# 04_EEPROM_FLASH.net
KiCad netlist of a schematic drawn in Altium Designer
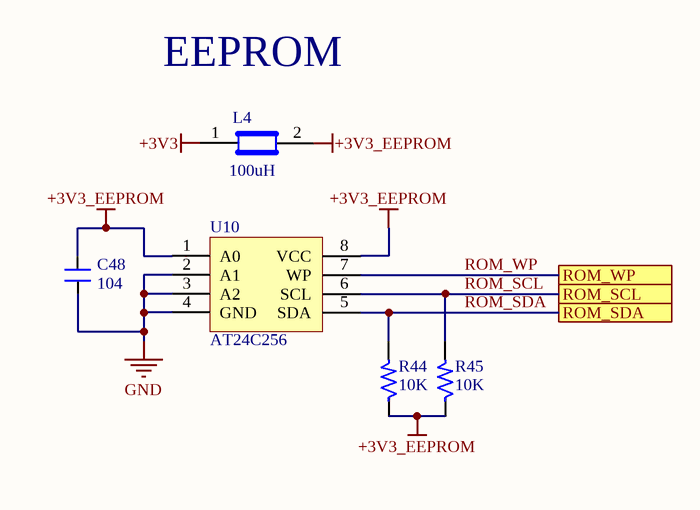
[diagram p0: [04] EEPROM_FLASH.SchDoc]

(export (version "E")
  (design (tool "Eeschema 10.0.6"))
  (components
    (comp (ref "C48")
      (value "104")
      (footprint "C0603 SMT")
      (description "Cap SMD")
      (libsource (lib "GPS_Traking_V1_1") (part "CM"))
    )
    (comp (ref "L4")
      (value "100uH")
      (footprint "R0805")
      (description "100uH 0805")
      (libsource (lib "GPS_Traking_V1_1") (part "Ferrite Bead"))
    )
    (comp (ref "R44")
      (value "10K")
      (footprint "R0603 -SMT")
      (description "Resistor SMD")
      (libsource (lib "GPS_Traking_V1_1") (part "RM"))
    )
    (comp (ref "R45")
      (value "10K")
      (footprint "R0603 -SMT")
      (description "Resistor SMD")
      (libsource (lib "GPS_Traking_V1_1") (part "RM"))
    )
    (comp (ref "U10")
      (value "AT24C256")
      (footprint "SO-8")
      (libsource (lib "GPS_Traking_V1_1") (part "AT24Cxx"))
    )
  )
  (nets
    (net (code "1") (name "+3V3") (class "Default")
      (node (ref "L4") (pin "1") (pinfunction "1_1") (pintype "passive"))
    )
    (net (code "2") (name "+3V3_EEPROM") (class "Default")
      (node (ref "C48") (pin "2") (pinfunction "2_2") (pintype "passive"))
      (node (ref "L4") (pin "2") (pinfunction "2_2") (pintype "passive"))
      (node (ref "R44") (pin "1") (pinfunction "1_1") (pintype "passive"))
      (node (ref "R45") (pin "1") (pinfunction "1_1") (pintype "passive"))
      (node (ref "U10") (pin "1") (pinfunction "A0_1") (pintype "passive"))
      (node (ref "U10") (pin "8") (pinfunction "VCC_8") (pintype "passive"))
    )
    (net (code "3") (name "/ROM_SCL") (class "Default")
      (node (ref "R45") (pin "2") (pinfunction "2_2") (pintype "passive"))
      (node (ref "U10") (pin "6") (pinfunction "SCL_6") (pintype "passive"))
    )
    (net (code "4") (name "/ROM_SDA") (class "Default")
      (node (ref "R44") (pin "2") (pinfunction "2_2") (pintype "passive"))
      (node (ref "U10") (pin "5") (pinfunction "SDA_5") (pintype "passive"))
    )
    (net (code "5") (name "/ROM_WP") (class "Default")
      (node (ref "U10") (pin "7") (pinfunction "WP_7") (pintype "passive"))
    )
    (net (code "6") (name "GND") (class "Default")
      (node (ref "C48") (pin "1") (pinfunction "1_1") (pintype "passive"))
      (node (ref "U10") (pin "2") (pinfunction "A1_2") (pintype "passive"))
      (node (ref "U10") (pin "3") (pinfunction "A2_3") (pintype "passive"))
      (node (ref "U10") (pin "4") (pinfunction "GND_4") (pintype "passive"))
    )
  )
)
